# Diag64Cart.net
KiCad netlist of a schematic drawn in EAGLE
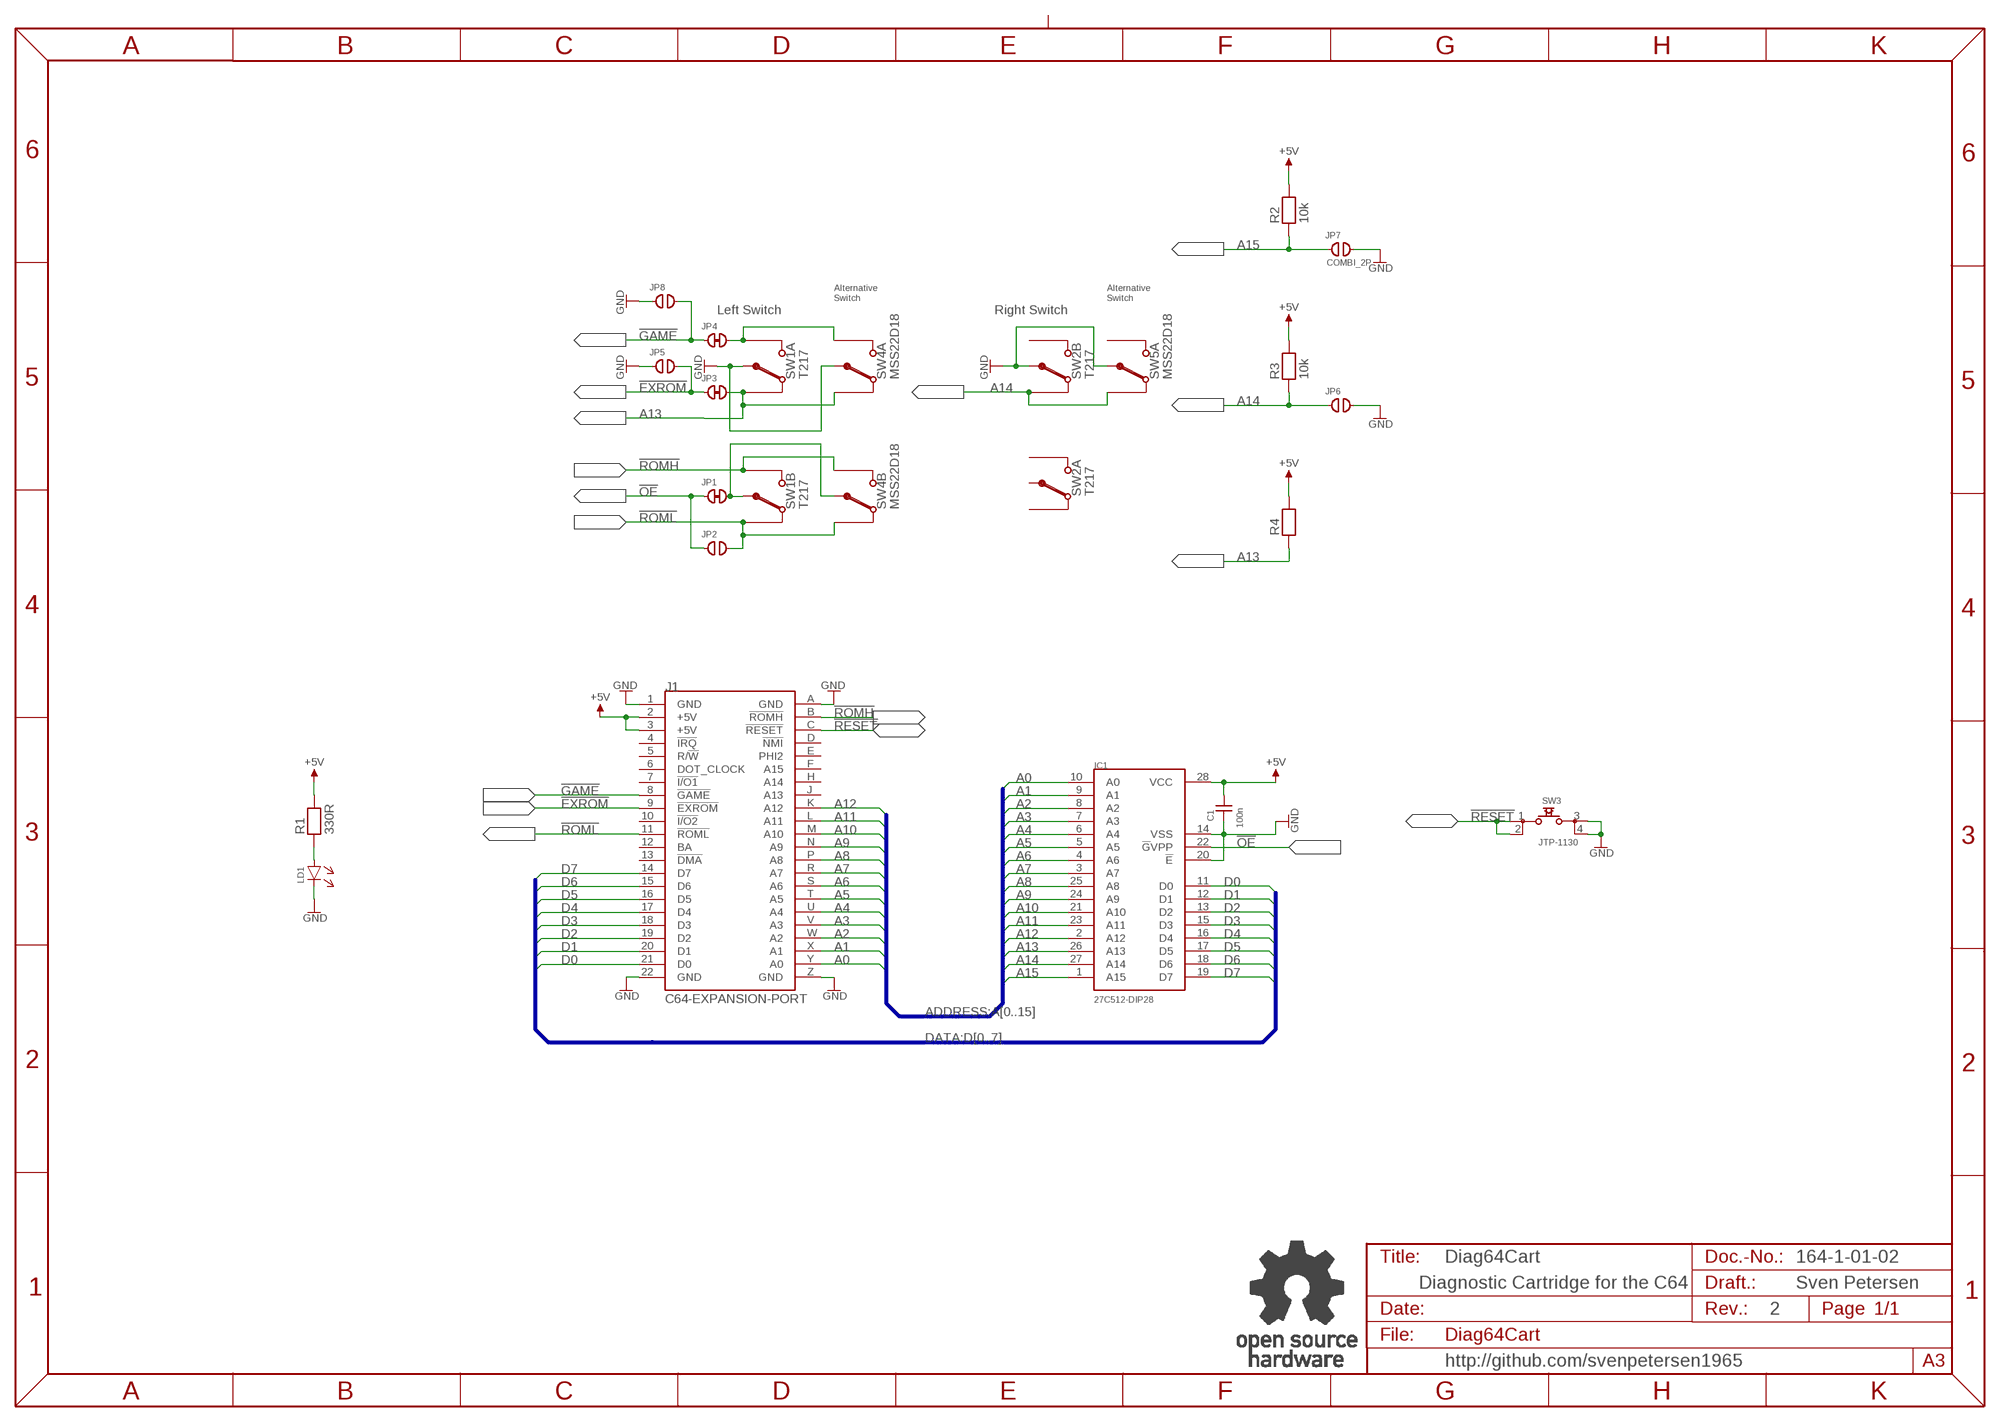
[diagram p0: schematic, sheet 1]

(export (version "E")
  (design (tool "Eeschema 10.0.6"))
  (components
    (comp (ref "C1")
      (value "100n")
      (footprint "eagle-import:C-2,5")
      (libsource (lib "eagle-import") (part "CAP01"))
    )
    (comp (ref "IC1")
      (value "27C512-DIP28")
      (footprint "eagle-import:DIL28-6")
      (libsource (lib "eagle-import") (part "M27C512-DIP28"))
    )
    (comp (ref "J1")
      (value "C64-EXPANSION-PORT")
      (footprint "eagle-import:EXPANSIO_SQ")
      (libsource (lib "eagle-import") (part "C64-EXPANSIONPNARROW"))
    )
    (comp (ref "JP1")
      (value "CLOSED")
      (footprint "eagle-import:CP_CL")
      (libsource (lib "eagle-import") (part "CLOSED"))
    )
    (comp (ref "JP2")
      (value "OPEN")
      (footprint "eagle-import:CP_OP")
      (libsource (lib "eagle-import") (part "OPEN"))
    )
    (comp (ref "JP3")
      (value "CLOSED")
      (footprint "eagle-import:CP_CL")
      (libsource (lib "eagle-import") (part "CLOSED"))
    )
    (comp (ref "JP4")
      (value "CLOSED")
      (footprint "eagle-import:CP_CL")
      (libsource (lib "eagle-import") (part "CLOSED"))
    )
    (comp (ref "JP5")
      (value "OPEN")
      (footprint "eagle-import:CP_OP")
      (libsource (lib "eagle-import") (part "OPEN"))
    )
    (comp (ref "JP6")
      (value "OPEN")
      (footprint "eagle-import:CP_OP")
      (libsource (lib "eagle-import") (part "OPEN"))
    )
    (comp (ref "JP7")
      (value "COMBI_2P")
      (footprint "eagle-import:COMBI-2P")
      (libsource (lib "eagle-import") (part "COMBI_2P"))
    )
    (comp (ref "JP8")
      (value "OPEN")
      (footprint "eagle-import:CP_OP")
      (libsource (lib "eagle-import") (part "OPEN"))
    )
    (comp (ref "LD1")
      (value "3MM")
      (footprint "eagle-import:3MM")
      (libsource (lib "eagle-import") (part "3MM"))
    )
    (comp (ref "R1")
      (value "330R")
      (footprint "eagle-import:R-10")
      (libsource (lib "eagle-import") (part "RES04"))
    )
    (comp (ref "R2")
      (value "10k")
      (footprint "eagle-import:R-10")
      (libsource (lib "eagle-import") (part "RES04"))
    )
    (comp (ref "R3")
      (value "10k")
      (footprint "eagle-import:R-10")
      (libsource (lib "eagle-import") (part "RES04"))
    )
    (comp (ref "R4")
      (value "10k")
      (footprint "eagle-import:R-10")
      (libsource (lib "eagle-import") (part "RES04"))
    )
    (comp (ref "SW1")
      (value "T217")
      (footprint "eagle-import:T217_SIDE")
      (libsource (lib "eagle-import") (part "T217"))
    )
    (comp (ref "SW2")
      (value "T217")
      (footprint "eagle-import:T217_SIDE")
      (libsource (lib "eagle-import") (part "T217"))
    )
    (comp (ref "SW3")
      (value "JTP-1130")
      (footprint "eagle-import:JTP-1130")
      (libsource (lib "eagle-import") (part "JTP-1130"))
    )
    (comp (ref "SW4")
      (value "MSS22D18")
      (footprint "eagle-import:DPDT_9MM")
      (libsource (lib "eagle-import") (part "DPDT_9MM"))
    )
    (comp (ref "SW5")
      (value "MSS22D18")
      (footprint "eagle-import:DPDT_9MM")
      (libsource (lib "eagle-import") (part "DPDT_9MM"))
    )
    (comp (ref "U$43")
      (value "OPEN_SOURCE_HW")
      (footprint "eagle-import:OPENHW")
      (libsource (lib "eagle-import") (part "OPEN_SOURCE_HW"))
    )
  )
  (nets
    (net (code "25") (name "+5V") (class "Default")
      (node (ref "C1") (pin "2") (pinfunction "2_2") (pintype "passive"))
      (node (ref "IC1") (pin "28") (pinfunction "VCC_28") (pintype "power_in"))
      (node (ref "J1") (pin "2") (pinfunction "+5V_2") (pintype "power_in"))
      (node (ref "J1") (pin "3") (pinfunction "+5V_3") (pintype "power_in"))
      (node (ref "R1") (pin "2") (pinfunction "2_2") (pintype "passive"))
      (node (ref "R2") (pin "2") (pinfunction "2_2") (pintype "passive"))
      (node (ref "R3") (pin "2") (pinfunction "2_2") (pintype "passive"))
      (node (ref "R4") (pin "2") (pinfunction "2_2") (pintype "passive"))
    )
    (net (code "26") (name "/A0") (class "Default")
      (node (ref "IC1") (pin "10") (pinfunction "A0_10") (pintype "input"))
      (node (ref "J1") (pin "Y") (pinfunction "A0_Y") (pintype "bidirectional"))
    )
    (net (code "27") (name "/A1") (class "Default")
      (node (ref "IC1") (pin "9") (pinfunction "A1_9") (pintype "input"))
      (node (ref "J1") (pin "X") (pinfunction "A1_X") (pintype "bidirectional"))
    )
    (net (code "28") (name "/A2") (class "Default")
      (node (ref "IC1") (pin "8") (pinfunction "A2_8") (pintype "input"))
      (node (ref "J1") (pin "W") (pinfunction "A2_W") (pintype "bidirectional"))
    )
    (net (code "29") (name "/A3") (class "Default")
      (node (ref "IC1") (pin "7") (pinfunction "A3_7") (pintype "input"))
      (node (ref "J1") (pin "V") (pinfunction "A3_V") (pintype "bidirectional"))
    )
    (net (code "30") (name "/A4") (class "Default")
      (node (ref "IC1") (pin "6") (pinfunction "A4_6") (pintype "input"))
      (node (ref "J1") (pin "U") (pinfunction "A4_U") (pintype "bidirectional"))
    )
    (net (code "31") (name "/A5") (class "Default")
      (node (ref "IC1") (pin "5") (pinfunction "A5_5") (pintype "input"))
      (node (ref "J1") (pin "T") (pinfunction "A5_T") (pintype "bidirectional"))
    )
    (net (code "32") (name "/A6") (class "Default")
      (node (ref "IC1") (pin "4") (pinfunction "A6_4") (pintype "input"))
      (node (ref "J1") (pin "S") (pinfunction "A6_S") (pintype "bidirectional"))
    )
    (net (code "33") (name "/A7") (class "Default")
      (node (ref "IC1") (pin "3") (pinfunction "A7_3") (pintype "input"))
      (node (ref "J1") (pin "R") (pinfunction "A7_R") (pintype "bidirectional"))
    )
    (net (code "34") (name "/A8") (class "Default")
      (node (ref "IC1") (pin "25") (pinfunction "A8_25") (pintype "input"))
      (node (ref "J1") (pin "P") (pinfunction "A8_P") (pintype "bidirectional"))
    )
    (net (code "35") (name "/A9") (class "Default")
      (node (ref "IC1") (pin "24") (pinfunction "A9_24") (pintype "input"))
      (node (ref "J1") (pin "N") (pinfunction "A9_N") (pintype "bidirectional"))
    )
    (net (code "36") (name "/A10") (class "Default")
      (node (ref "IC1") (pin "21") (pinfunction "A10_21") (pintype "input"))
      (node (ref "J1") (pin "M") (pinfunction "A10_M") (pintype "bidirectional"))
    )
    (net (code "37") (name "/A11") (class "Default")
      (node (ref "IC1") (pin "23") (pinfunction "A11_23") (pintype "input"))
      (node (ref "J1") (pin "L") (pinfunction "A11_L") (pintype "bidirectional"))
    )
    (net (code "38") (name "/A12") (class "Default")
      (node (ref "IC1") (pin "2") (pinfunction "A12_2") (pintype "input"))
      (node (ref "J1") (pin "K") (pinfunction "A12_K") (pintype "bidirectional"))
    )
    (net (code "39") (name "/A13") (class "Default")
      (node (ref "IC1") (pin "26") (pinfunction "A13_26") (pintype "input"))
      (node (ref "JP3") (pin "2") (pinfunction "2_2") (pintype "passive"))
      (node (ref "R4") (pin "1") (pinfunction "1_1") (pintype "passive"))
      (node (ref "SW1") (pin "DWN1") (pinfunction "DWN_DWN1") (pintype "bidirectional"))
      (node (ref "SW4") (pin "3") (pinfunction "DWN_3") (pintype "bidirectional"))
    )
    (net (code "40") (name "/A14") (class "Default")
      (node (ref "IC1") (pin "27") (pinfunction "A14_27") (pintype "input"))
      (node (ref "JP6") (pin "1") (pinfunction "1_1") (pintype "passive"))
      (node (ref "R3") (pin "1") (pinfunction "1_1") (pintype "passive"))
      (node (ref "SW2") (pin "DWN2") (pinfunction "DWN_DWN2") (pintype "bidirectional"))
      (node (ref "SW5") (pin "3") (pinfunction "DWN_3") (pintype "bidirectional"))
    )
    (net (code "41") (name "/A15") (class "Default")
      (node (ref "IC1") (pin "1") (pinfunction "A15_1") (pintype "input"))
      (node (ref "JP7") (pin "1") (pinfunction "1_1") (pintype "passive"))
      (node (ref "R2") (pin "1") (pinfunction "1_1") (pintype "passive"))
    )
    (net (code "43") (name "/D0") (class "Default")
      (node (ref "IC1") (pin "11") (pinfunction "D0_11") (pintype "bidirectional"))
      (node (ref "J1") (pin "21") (pinfunction "D0_21") (pintype "bidirectional"))
    )
    (net (code "44") (name "/D1") (class "Default")
      (node (ref "IC1") (pin "12") (pinfunction "D1_12") (pintype "bidirectional"))
      (node (ref "J1") (pin "20") (pinfunction "D1_20") (pintype "bidirectional"))
    )
    (net (code "45") (name "/D2") (class "Default")
      (node (ref "IC1") (pin "13") (pinfunction "D2_13") (pintype "bidirectional"))
      (node (ref "J1") (pin "19") (pinfunction "D2_19") (pintype "bidirectional"))
    )
    (net (code "46") (name "/D3") (class "Default")
      (node (ref "IC1") (pin "15") (pinfunction "D3_15") (pintype "bidirectional"))
      (node (ref "J1") (pin "18") (pinfunction "D3_18") (pintype "bidirectional"))
    )
    (net (code "47") (name "/D4") (class "Default")
      (node (ref "IC1") (pin "16") (pinfunction "D4_16") (pintype "bidirectional"))
      (node (ref "J1") (pin "17") (pinfunction "D4_17") (pintype "bidirectional"))
    )
    (net (code "48") (name "/D5") (class "Default")
      (node (ref "IC1") (pin "17") (pinfunction "D5_17") (pintype "bidirectional"))
      (node (ref "J1") (pin "16") (pinfunction "D5_16") (pintype "bidirectional"))
    )
    (net (code "49") (name "/D6") (class "Default")
      (node (ref "IC1") (pin "18") (pinfunction "D6_18") (pintype "bidirectional"))
      (node (ref "J1") (pin "15") (pinfunction "D6_15") (pintype "bidirectional"))
    )
    (net (code "50") (name "/D7") (class "Default")
      (node (ref "IC1") (pin "19") (pinfunction "D7_19") (pintype "bidirectional"))
      (node (ref "J1") (pin "14") (pinfunction "D7_14") (pintype "bidirectional"))
    )
    (net (code "52") (name "/~{EXROM}") (class "Default")
      (node (ref "J1") (pin "9") (pinfunction "~{EXROM}_9") (pintype "input"))
      (node (ref "JP3") (pin "1") (pinfunction "1_1") (pintype "passive"))
      (node (ref "JP5") (pin "2") (pinfunction "2_2") (pintype "passive"))
    )
    (net (code "53") (name "/~{GAME}") (class "Default")
      (node (ref "J1") (pin "8") (pinfunction "~{GAME}_8") (pintype "input"))
      (node (ref "JP4") (pin "1") (pinfunction "1_1") (pintype "passive"))
      (node (ref "JP8") (pin "2") (pinfunction "2_2") (pintype "passive"))
    )
    (net (code "54") (name "/~{OE}") (class "Default")
      (node (ref "IC1") (pin "22") (pinfunction "~{G}VPP_22") (pintype "input"))
      (node (ref "JP1") (pin "1") (pinfunction "1_1") (pintype "passive"))
      (node (ref "JP2") (pin "1") (pinfunction "1_1") (pintype "passive"))
    )
    (net (code "55") (name "/~{RESET}") (class "Default")
      (node (ref "J1") (pin "C") (pinfunction "~{RESET}_C") (pintype "open_collector"))
      (node (ref "SW3") (pin "1") (pinfunction "1_1") (pintype "passive"))
      (node (ref "SW3") (pin "2") (pinfunction "2_2") (pintype "passive"))
    )
    (net (code "56") (name "/~{ROMH}") (class "Default")
      (node (ref "J1") (pin "B") (pinfunction "~{ROMH}_B") (pintype "output"))
      (node (ref "SW1") (pin "UP2") (pinfunction "UP_UP2") (pintype "bidirectional"))
      (node (ref "SW4") (pin "6") (pinfunction "UP_6") (pintype "bidirectional"))
    )
    (net (code "57") (name "/~{ROML}") (class "Default")
      (node (ref "J1") (pin "11") (pinfunction "~{ROML}_11") (pintype "output"))
      (node (ref "JP2") (pin "2") (pinfunction "2_2") (pintype "passive"))
      (node (ref "SW1") (pin "DWN2") (pinfunction "DWN_DWN2") (pintype "bidirectional"))
      (node (ref "SW4") (pin "4") (pinfunction "DWN_4") (pintype "bidirectional"))
    )
    (net (code "58") (name "GND") (class "Default")
      (node (ref "C1") (pin "1") (pinfunction "1_1") (pintype "passive"))
      (node (ref "IC1") (pin "14") (pinfunction "VSS_14") (pintype "power_in"))
      (node (ref "IC1") (pin "20") (pinfunction "~{E}_20") (pintype "input"))
      (node (ref "J1") (pin "1") (pinfunction "GND_1") (pintype "power_in"))
      (node (ref "J1") (pin "22") (pinfunction "GND_22") (pintype "power_in"))
      (node (ref "J1") (pin "A") (pinfunction "GND_A") (pintype "power_in"))
      (node (ref "J1") (pin "Z") (pinfunction "GND_Z") (pintype "power_in"))
      (node (ref "JP5") (pin "1") (pinfunction "1_1") (pintype "passive"))
      (node (ref "JP6") (pin "2") (pinfunction "2_2") (pintype "passive"))
      (node (ref "JP7") (pin "2") (pinfunction "2_2") (pintype "passive"))
      (node (ref "JP8") (pin "1") (pinfunction "1_1") (pintype "passive"))
      (node (ref "LD1") (pin "C") (pinfunction "K_C") (pintype "bidirectional"))
      (node (ref "SW1") (pin "COM1") (pinfunction "COM_COM1") (pintype "bidirectional"))
      (node (ref "SW2") (pin "COM2") (pinfunction "COM_COM2") (pintype "bidirectional"))
      (node (ref "SW3") (pin "3") (pinfunction "3_3") (pintype "passive"))
      (node (ref "SW3") (pin "4") (pinfunction "4_4") (pintype "passive"))
      (node (ref "SW4") (pin "2") (pinfunction "COM_2") (pintype "bidirectional"))
      (node (ref "SW5") (pin "2") (pinfunction "COM_2") (pintype "bidirectional"))
    )
    (net (code "59") (name "Net-(LD1-PadA)") (class "Default")
      (node (ref "LD1") (pin "A") (pinfunction "A_A") (pintype "bidirectional"))
      (node (ref "R1") (pin "1") (pinfunction "1_1") (pintype "passive"))
    )
    (net (code "60") (name "Net-(SW1A-UP)") (class "Default")
      (node (ref "JP4") (pin "2") (pinfunction "2_2") (pintype "passive"))
      (node (ref "SW1") (pin "UP1") (pinfunction "UP_UP1") (pintype "bidirectional"))
      (node (ref "SW4") (pin "1") (pinfunction "UP_1") (pintype "bidirectional"))
    )
    (net (code "61") (name "Net-(SW1B-COM)") (class "Default")
      (node (ref "JP1") (pin "2") (pinfunction "2_2") (pintype "passive"))
      (node (ref "SW1") (pin "COM2") (pinfunction "COM_COM2") (pintype "bidirectional"))
      (node (ref "SW4") (pin "5") (pinfunction "COM_5") (pintype "bidirectional"))
    )
    (net (code "62") (name "unconnected-(J1-A13-PadJ)") (class "Default")
      (node (ref "J1") (pin "J") (pinfunction "A13_J") (pintype "bidirectional"))
    )
    (net (code "63") (name "unconnected-(J1-A14-PadH)") (class "Default")
      (node (ref "J1") (pin "H") (pinfunction "A14_H") (pintype "bidirectional"))
    )
    (net (code "64") (name "unconnected-(J1-A15-PadF)") (class "Default")
      (node (ref "J1") (pin "F") (pinfunction "A15_F") (pintype "bidirectional"))
    )
    (net (code "65") (name "unconnected-(J1-BA-Pad12)") (class "Default")
      (node (ref "J1") (pin "12") (pinfunction "BA_12") (pintype "output"))
    )
    (net (code "66") (name "unconnected-(J1-DOT_CLOCK-Pad6)") (class "Default")
      (node (ref "J1") (pin "6") (pinfunction "DOT_CLOCK_6") (pintype "output"))
    )
    (net (code "67") (name "unconnected-(J1-PHI2-PadE)") (class "Default")
      (node (ref "J1") (pin "E") (pinfunction "PHI2_E") (pintype "output"))
    )
    (net (code "68") (name "unconnected-(J1-R{slash}~{W}-Pad5)") (class "Default")
      (node (ref "J1") (pin "5") (pinfunction "R/~{W}_5") (pintype "output"))
    )
    (net (code "69") (name "unconnected-(J1-~{DMA}-Pad13)") (class "Default")
      (node (ref "J1") (pin "13") (pinfunction "~{DMA}_13") (pintype "input"))
    )
    (net (code "70") (name "unconnected-(J1-~{IRQ}-Pad4)") (class "Default")
      (node (ref "J1") (pin "4") (pinfunction "~{IRQ}_4") (pintype "input"))
    )
    (net (code "71") (name "unconnected-(J1-~{I{slash}O1}-Pad7)") (class "Default")
      (node (ref "J1") (pin "7") (pinfunction "~{I/O1}_7") (pintype "output"))
    )
    (net (code "72") (name "unconnected-(J1-~{I{slash}O2}-Pad10)") (class "Default")
      (node (ref "J1") (pin "10") (pinfunction "~{I/O2}_10") (pintype "output"))
    )
    (net (code "73") (name "unconnected-(J1-~{NMI}-PadD)") (class "Default")
      (node (ref "J1") (pin "D") (pinfunction "~{NMI}_D") (pintype "input"))
    )
    (net (code "74") (name "unconnected-(SW2A-COM-PadCOM1)") (class "Default")
      (node (ref "SW2") (pin "COM1") (pinfunction "COM_COM1") (pintype "bidirectional"))
    )
    (net (code "75") (name "unconnected-(SW2A-DWN-PadDWN1)") (class "Default")
      (node (ref "SW2") (pin "DWN1") (pinfunction "DWN_DWN1") (pintype "bidirectional"))
    )
    (net (code "76") (name "unconnected-(SW2A-UP-PadUP1)") (class "Default")
      (node (ref "SW2") (pin "UP1") (pinfunction "UP_UP1") (pintype "bidirectional"))
    )
    (net (code "77") (name "unconnected-(SW2B-UP-PadUP2)") (class "Default")
      (node (ref "SW2") (pin "UP2") (pinfunction "UP_UP2") (pintype "bidirectional"))
    )
    (net (code "78") (name "unconnected-(SW5A-UP-Pad1)") (class "Default")
      (node (ref "SW5") (pin "1") (pinfunction "UP_1") (pintype "bidirectional"))
    )
  )
)
